# DMX.net
KiCad netlist of a schematic drawn in Altium Designer
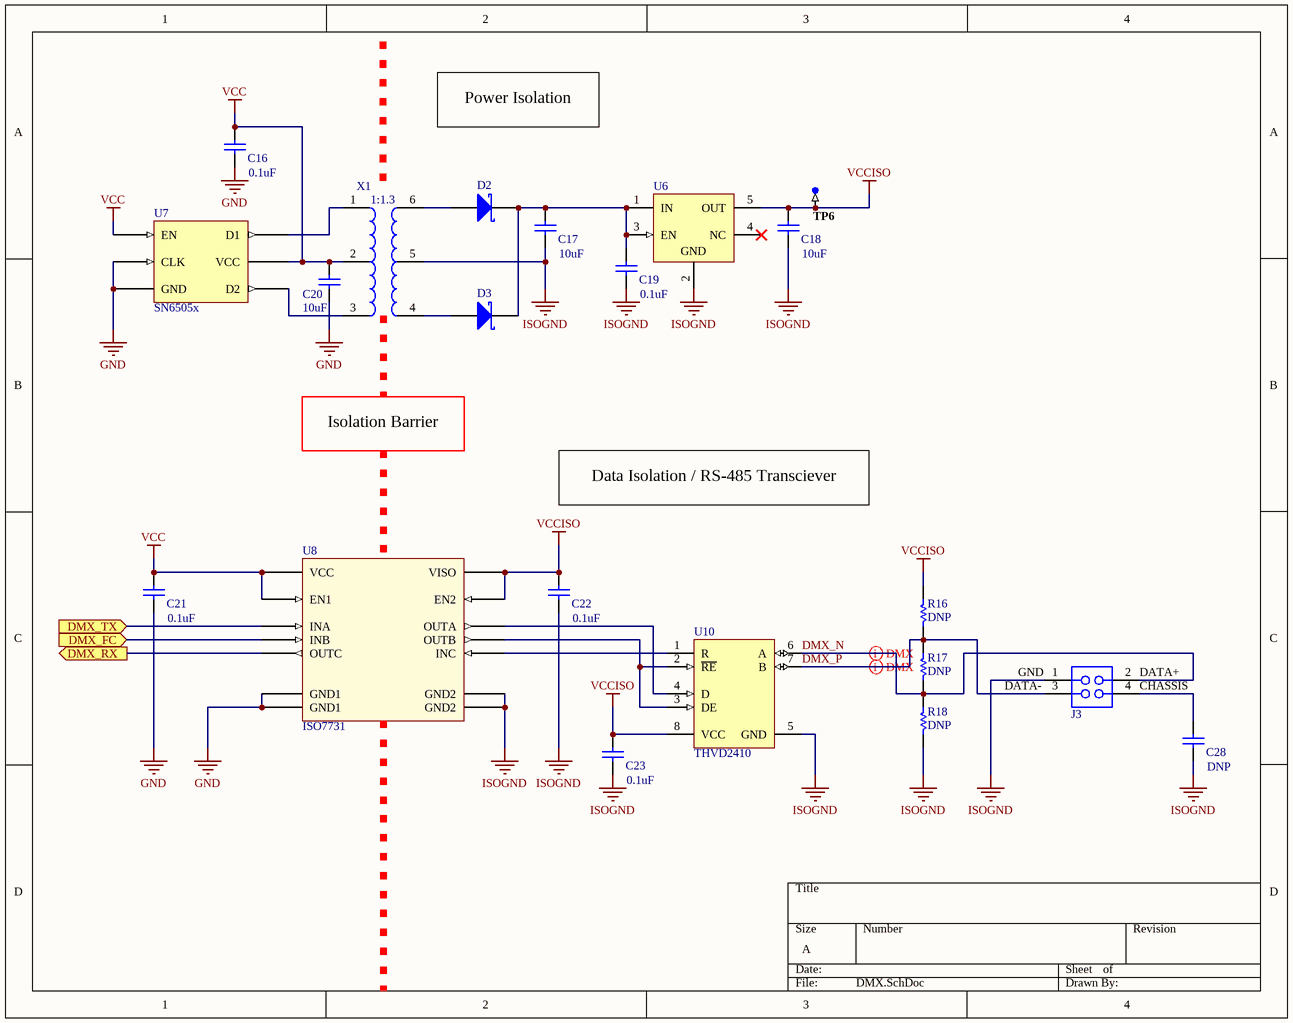
[diagram p0: DMX.SchDoc]

(export (version "E")
  (design (tool "Eeschema 10.0.6"))
  (components
    (comp (ref "C16")
      (value "0.1uF")
      (footprint "CAPC0603(1608)100_L")
      (description "CAP 27pF 16V ±0.5pF 0603 (1608 Metric) Thickness 1mm SMD")
      (fields (field (name "TOLERANCE") "Â±0.5pF"))
      (libsource (lib "Altium Content Vault") (part "CMP-1035-00873-1"))
    )
    (comp (ref "C17")
      (value "10uF")
      (footprint "CAPC0603(1608)100_L")
      (description "CAP 27pF 16V ±0.5pF 0603 (1608 Metric) Thickness 1mm SMD")
      (fields (field (name "TOLERANCE") "Â±0.5pF"))
      (libsource (lib "Altium Content Vault") (part "CMP-1035-00873-1"))
    )
    (comp (ref "C18")
      (value "10uF")
      (footprint "CAPC0603(1608)100_L")
      (description "CAP 27pF 16V ±0.5pF 0603 (1608 Metric) Thickness 1mm SMD")
      (fields (field (name "TOLERANCE") "Â±0.5pF"))
      (libsource (lib "Altium Content Vault") (part "CMP-1035-00873-1"))
    )
    (comp (ref "C19")
      (value "0.1uF")
      (footprint "CAPC0603(1608)100_L")
      (description "CAP 27pF 16V ±0.5pF 0603 (1608 Metric) Thickness 1mm SMD")
      (fields (field (name "TOLERANCE") "Â±0.5pF"))
      (libsource (lib "Altium Content Vault") (part "CMP-1035-00873-1"))
    )
    (comp (ref "C20")
      (value "10uF")
      (footprint "CAPC0603(1608)100_L")
      (description "CAP 27pF 16V ±0.5pF 0603 (1608 Metric) Thickness 1mm SMD")
      (fields (field (name "TOLERANCE") "Â±0.5pF"))
      (libsource (lib "Altium Content Vault") (part "CMP-1035-00873-1"))
    )
    (comp (ref "C21")
      (value "0.1uF")
      (footprint "CAPC0603(1608)100_L")
      (description "CAP 27pF 16V ±0.5pF 0603 (1608 Metric) Thickness 1mm SMD")
      (fields (field (name "TOLERANCE") "Â±0.5pF"))
      (libsource (lib "Altium Content Vault") (part "CMP-1035-00873-1"))
    )
    (comp (ref "C22")
      (value "0.1uF")
      (footprint "CAPC0603(1608)100_L")
      (description "CAP 27pF 16V ±0.5pF 0603 (1608 Metric) Thickness 1mm SMD")
      (fields (field (name "TOLERANCE") "Â±0.5pF"))
      (libsource (lib "Altium Content Vault") (part "CMP-1035-00873-1"))
    )
    (comp (ref "C23")
      (value "0.1uF")
      (footprint "CAPC0603(1608)100_L")
      (description "CAP 27pF 16V ±0.5pF 0603 (1608 Metric) Thickness 1mm SMD")
      (fields (field (name "TOLERANCE") "Â±0.5pF"))
      (libsource (lib "Altium Content Vault") (part "CMP-1035-00873-1"))
    )
    (comp (ref "C28")
      (value "DNP")
      (footprint "CAPC0603(1608)100_L")
      (description "CAP 27pF 16V ±0.5pF 0603 (1608 Metric) Thickness 1mm SMD")
      (fields (field (name "TOLERANCE") "Â±0.5pF"))
      (libsource (lib "Altium Content Vault") (part "CMP-1035-00873-1"))
    )
    (comp (ref "D2")
      (value "MBR0520L")
      (footprint "ONSC-SOD-123-2-425-04_V")
      (description "Schottky Diode, 20V, 0.2A, 2-pin SOD-123, RoHS, Tape and Reel")
      (fields (field (name "MANUFACTURER") "FairchildSemiconductor"))
      (libsource (lib "Altium Content Vault") (part "CMP-2000-04926-1"))
    )
    (comp (ref "D3")
      (value "MBR0520L")
      (footprint "ONSC-SOD-123-2-425-04_V")
      (description "Schottky Diode, 20V, 0.2A, 2-pin SOD-123, RoHS, Tape and Reel")
      (fields (field (name "MANUFACTURER") "FairchildSemiconductor"))
      (libsource (lib "Altium Content Vault") (part "CMP-2000-04926-1"))
    )
    (comp (ref "J3")
      (value "SSM-102-F-DV")
      (footprint "SMTC-SSM-102-X-DV")
      (description "Tiger Claw(TM) Surface Mount Socket, Vertical, -55 to 125 degC, 2.54 mm Pitch, 4-Pin, Female, RoHS")
      (fields (field (name "MANUFACTURER") "Samtec"))
      (libsource (lib "Altium Content Vault") (part "CMP-1023-00199-1"))
    )
    (comp (ref "R16")
      (value "DNP")
      (footprint "RESC0603(1608)_N")
      (description "300K 0.1W 5% 0603 (1608 Metric)  SMD")
      (fields (field (name "POWER") "0.1 W") (field (name "TOLERANCE") "5 %"))
      (libsource (lib "Altium Content Vault") (part "CMP-1012-00133-1"))
    )
    (comp (ref "R17")
      (value "DNP")
      (footprint "RESC0603(1608)_N")
      (description "300K 0.1W 5% 0603 (1608 Metric)  SMD")
      (fields (field (name "POWER") "0.1 W") (field (name "TOLERANCE") "5 %"))
      (libsource (lib "Altium Content Vault") (part "CMP-1012-00133-1"))
    )
    (comp (ref "R18")
      (value "DNP")
      (footprint "RESC0603(1608)_N")
      (description "300K 0.1W 5% 0603 (1608 Metric)  SMD")
      (fields (field (name "POWER") "0.1 W") (field (name "TOLERANCE") "5 %"))
      (libsource (lib "Altium Content Vault") (part "CMP-1012-00133-1"))
    )
    (comp (ref "TP6")
      (value "TP-SM-C-100")
      (footprint "TP-SM-C-100")
      (description "Test Point, Surface Mount, Circular, Pad Diameter 1 mm")
      (fields (field (name "MANUFACTURER") "No Vendor"))
      (libsource (lib "Altium Content Vault") (part "CMP-0484-00002-2"))
    )
    (comp (ref "U6")
      (value "TPS76333DBVTG4")
      (footprint "TI-DBV5_M")
      (fields (field (name "MANUFACTURER") "Texas Instruments"))
      (libsource (lib "Altium Content Vault") (part "CMP-0394-00562-1"))
    )
    (comp (ref "U7")
      (value "SN6505x")
      (footprint "SOT-23-6")
      (libsource (lib "Texas Instruments") (part "SN6505x"))
    )
    (comp (ref "U8")
      (value "ISO7731")
      (footprint "SOIC (16)")
      (libsource (lib "Texas Instruments") (part "ISO7731"))
    )
    (comp (ref "U10")
      (value "THVD2410")
      (footprint "D0008A_N")
      (fields (field (name "MANUFACTURER") "Texas Instruments") (field (name "PARTNUMBER") "SN65HVD75DR"))
      (libsource (lib "Altium Content Vault") (part "CMP-0694-00003-2"))
    )
    (comp (ref "X1")
      (value "750313638")
      (footprint "750313638")
      (libsource (lib "Wurth Electronics") (part "750313638"))
    )
  )
  (nets
    (net (code "1") (name "/DMX_FC") (class "Default")
      (node (ref "U8") (pin "4") (pinfunction "INB_4") (pintype "input"))
    )
    (net (code "2") (name "/DMX_N") (class "Default")
      (node (ref "J3") (pin "2") (pinfunction "2_2") (pintype "passive"))
      (node (ref "R17") (pin "1") (pinfunction "1_1") (pintype "passive"))
      (node (ref "R18") (pin "1") (pinfunction "1_1") (pintype "passive"))
      (node (ref "U10") (pin "6") (pinfunction "A_6") (pintype "bidirectional"))
    )
    (net (code "3") (name "/DMX_P") (class "Default")
      (node (ref "J3") (pin "3") (pinfunction "3_3") (pintype "passive"))
      (node (ref "R16") (pin "2") (pinfunction "2_2") (pintype "passive"))
      (node (ref "R17") (pin "2") (pinfunction "2_2") (pintype "passive"))
      (node (ref "U10") (pin "7") (pinfunction "B_7") (pintype "bidirectional"))
    )
    (net (code "4") (name "/DMX_RX") (class "Default")
      (node (ref "U8") (pin "5") (pinfunction "OUTC_5") (pintype "output"))
    )
    (net (code "5") (name "/DMX_TX") (class "Default")
      (node (ref "U8") (pin "3") (pinfunction "INA_3") (pintype "input"))
    )
    (net (code "6") (name "GND") (class "Default")
      (node (ref "C16") (pin "1") (pinfunction "1_1") (pintype "passive"))
      (node (ref "C20") (pin "1") (pinfunction "1_1") (pintype "passive"))
      (node (ref "C21") (pin "1") (pinfunction "1_1") (pintype "passive"))
      (node (ref "U7") (pin "4") (pinfunction "GND_4") (pintype "power_in"))
      (node (ref "U7") (pin "6") (pinfunction "CLK_6") (pintype "input"))
      (node (ref "U8") (pin "2") (pinfunction "GND1_2") (pintype "power_in"))
      (node (ref "U8") (pin "8") (pinfunction "GND1_8") (pintype "power_in"))
    )
    (net (code "7") (name "ISOGND") (class "Default")
      (node (ref "C17") (pin "1") (pinfunction "1_1") (pintype "passive"))
      (node (ref "C18") (pin "1") (pinfunction "1_1") (pintype "passive"))
      (node (ref "C19") (pin "1") (pinfunction "1_1") (pintype "passive"))
      (node (ref "C22") (pin "1") (pinfunction "1_1") (pintype "passive"))
      (node (ref "C23") (pin "1") (pinfunction "1_1") (pintype "passive"))
      (node (ref "C28") (pin "1") (pinfunction "1_1") (pintype "passive"))
      (node (ref "J3") (pin "1") (pinfunction "1_1") (pintype "passive"))
      (node (ref "R18") (pin "2") (pinfunction "2_2") (pintype "passive"))
      (node (ref "U10") (pin "5") (pinfunction "GND_5") (pintype "power_in"))
      (node (ref "U6") (pin "2") (pinfunction "GND_2") (pintype "power_in"))
      (node (ref "U8") (pin "15") (pinfunction "GND2_15") (pintype "power_in"))
      (node (ref "U8") (pin "9") (pinfunction "GND2_9") (pintype "power_in"))
      (node (ref "X1") (pin "5") (pinfunction "5_5") (pintype "passive"))
    )
    (net (code "8") (name "Net-(C28-Pad2)") (class "Default")
      (node (ref "C28") (pin "2") (pinfunction "2_2") (pintype "passive"))
      (node (ref "J3") (pin "4") (pinfunction "4_4") (pintype "passive"))
    )
    (net (code "9") (name "Net-(D2-A)") (class "Default")
      (node (ref "D2") (pin "2") (pinfunction "A_2") (pintype "passive"))
      (node (ref "X1") (pin "6") (pinfunction "6_6") (pintype "passive"))
    )
    (net (code "10") (name "Net-(D2-K)") (class "Default")
      (node (ref "C17") (pin "2") (pinfunction "2_2") (pintype "passive"))
      (node (ref "C19") (pin "2") (pinfunction "2_2") (pintype "passive"))
      (node (ref "D2") (pin "1") (pinfunction "K_1") (pintype "passive"))
      (node (ref "D3") (pin "1") (pinfunction "K_1") (pintype "passive"))
      (node (ref "U6") (pin "1") (pinfunction "IN_1") (pintype "power_in"))
      (node (ref "U6") (pin "3") (pinfunction "EN_3") (pintype "input"))
    )
    (net (code "11") (name "Net-(D3-A)") (class "Default")
      (node (ref "D3") (pin "2") (pinfunction "A_2") (pintype "passive"))
      (node (ref "X1") (pin "4") (pinfunction "4_4") (pintype "passive"))
    )
    (net (code "12") (name "Net-(U7-D1)") (class "Default")
      (node (ref "U7") (pin "1") (pinfunction "D1_1") (pintype "output"))
      (node (ref "X1") (pin "1") (pinfunction "1_1") (pintype "passive"))
    )
    (net (code "13") (name "Net-(U7-D2)") (class "Default")
      (node (ref "U7") (pin "3") (pinfunction "D2_3") (pintype "output"))
      (node (ref "X1") (pin "3") (pinfunction "3_3") (pintype "passive"))
    )
    (net (code "14") (name "Net-(U10-D)") (class "Default")
      (node (ref "U10") (pin "4") (pinfunction "D_4") (pintype "input"))
      (node (ref "U8") (pin "14") (pinfunction "OUTA_14") (pintype "output"))
    )
    (net (code "15") (name "Net-(U10-DE)") (class "Default")
      (node (ref "U10") (pin "2") (pinfunction "~{RE}_2") (pintype "input"))
      (node (ref "U10") (pin "3") (pinfunction "DE_3") (pintype "input"))
      (node (ref "U8") (pin "13") (pinfunction "OUTB_13") (pintype "output"))
    )
    (net (code "16") (name "Net-(U10-R)") (class "Default")
      (node (ref "U10") (pin "1") (pinfunction "R_1") (pintype "tri_state"))
      (node (ref "U8") (pin "12") (pinfunction "INC_12") (pintype "input"))
    )
    (net (code "17") (name "VCC") (class "Default")
      (node (ref "C16") (pin "2") (pinfunction "2_2") (pintype "passive"))
      (node (ref "C20") (pin "2") (pinfunction "2_2") (pintype "passive"))
      (node (ref "C21") (pin "2") (pinfunction "2_2") (pintype "passive"))
      (node (ref "U7") (pin "2") (pinfunction "VCC_2") (pintype "power_in"))
      (node (ref "U7") (pin "5") (pinfunction "EN_5") (pintype "input"))
      (node (ref "U8") (pin "1") (pinfunction "VCC_1") (pintype "power_in"))
      (node (ref "U8") (pin "7") (pinfunction "EN1_7") (pintype "input"))
      (node (ref "X1") (pin "2") (pinfunction "2_2") (pintype "passive"))
    )
    (net (code "18") (name "VCCISO") (class "Default")
      (node (ref "C18") (pin "2") (pinfunction "2_2") (pintype "passive"))
      (node (ref "C22") (pin "2") (pinfunction "2_2") (pintype "passive"))
      (node (ref "C23") (pin "2") (pinfunction "2_2") (pintype "passive"))
      (node (ref "R16") (pin "1") (pinfunction "1_1") (pintype "passive"))
      (node (ref "TP6") (pin "1") (pinfunction "1_1") (pintype "input"))
      (node (ref "U10") (pin "8") (pinfunction "VCC_8") (pintype "power_in"))
      (node (ref "U6") (pin "5") (pinfunction "OUT_5") (pintype "power_in"))
      (node (ref "U8") (pin "10") (pinfunction "EN2_10") (pintype "input"))
      (node (ref "U8") (pin "16") (pinfunction "VISO_16") (pintype "power_in"))
    )
    (net (code "19") (name "unconnected-(U6-NC-Pad4)") (class "Default")
      (node (ref "U6") (pin "4") (pinfunction "NC_4") (pintype "passive+no_connect"))
    )
    (net (code "20") (name "unconnected-(U8-NC-Pad6)") (class "Default")
      (node (ref "U8") (pin "6") (pinfunction "NC_6") (pintype "passive"))
    )
    (net (code "21") (name "unconnected-(U8-NC-Pad11)") (class "Default")
      (node (ref "U8") (pin "11") (pinfunction "NC_11") (pintype "passive"))
    )
  )
)
